# Quad_Board.net
KiCad netlist of a schematic drawn in EAGLE
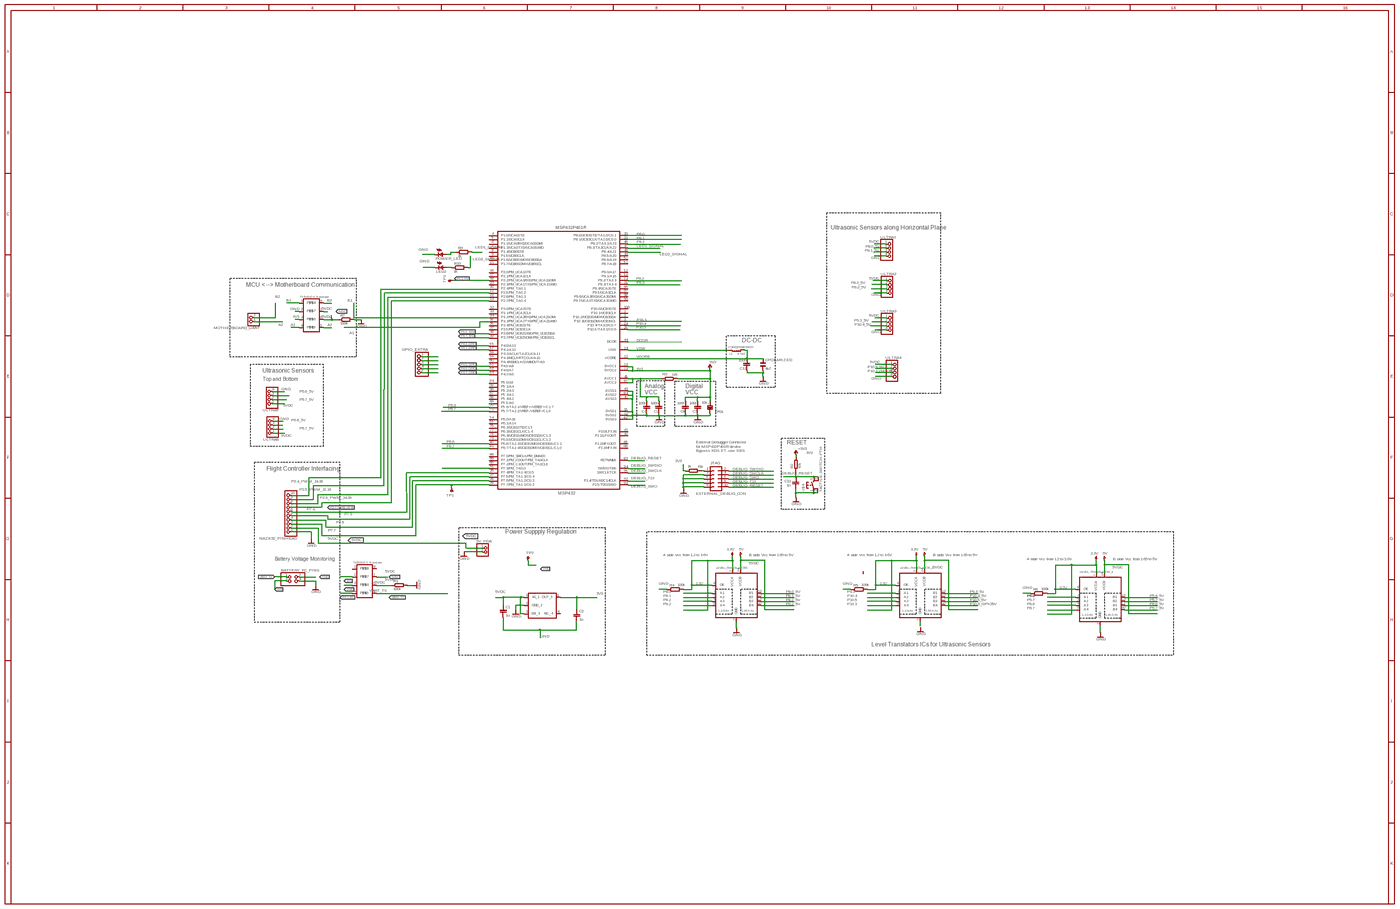
[diagram p0: schematic, sheet 1, overview]
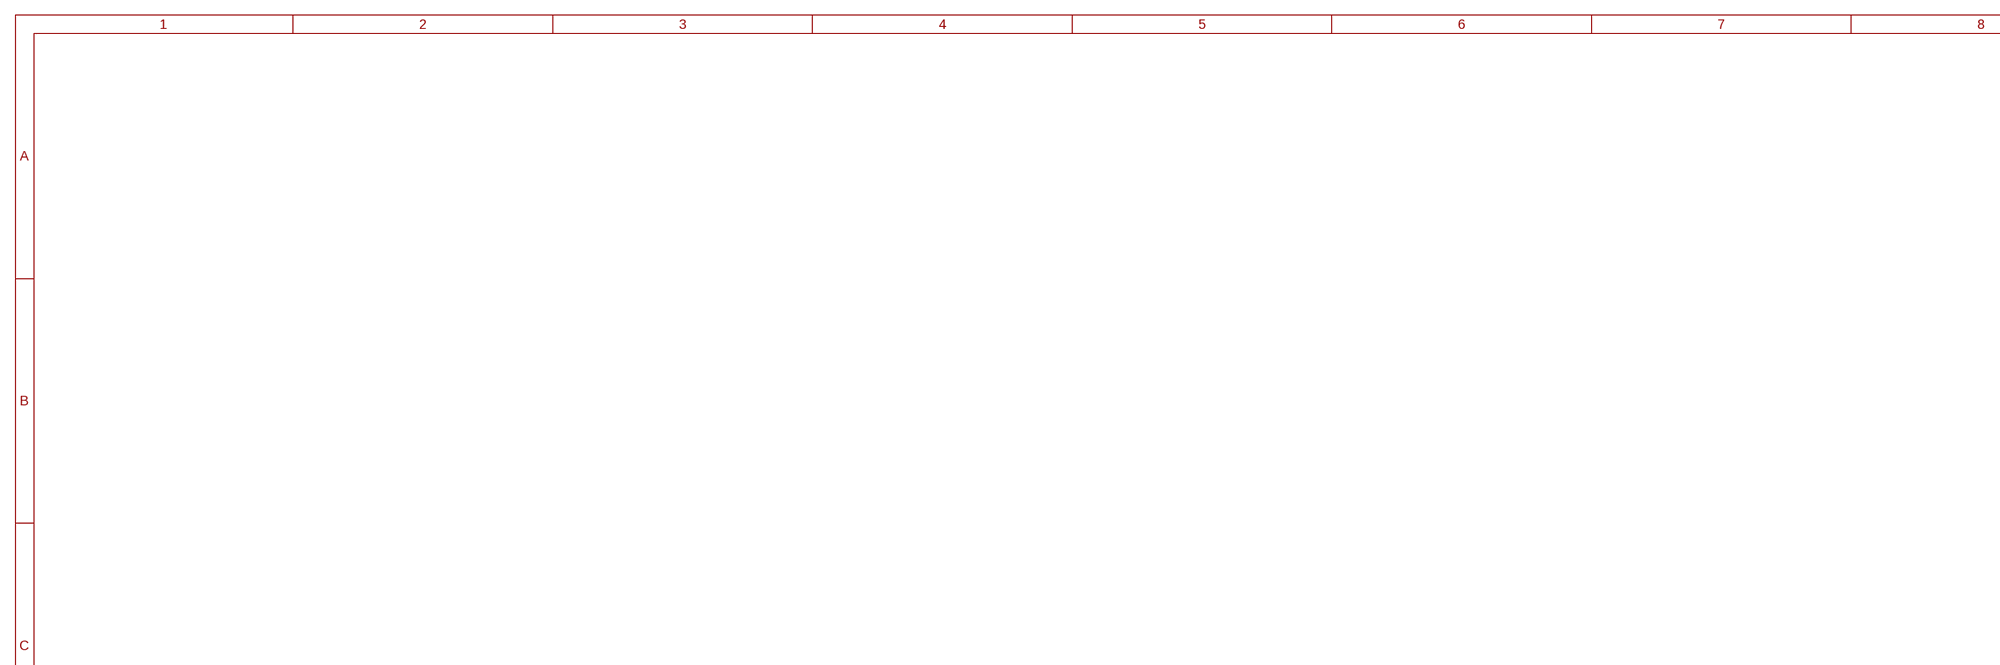
[diagram p1: schematic, sheet 1, part 1 of 4]
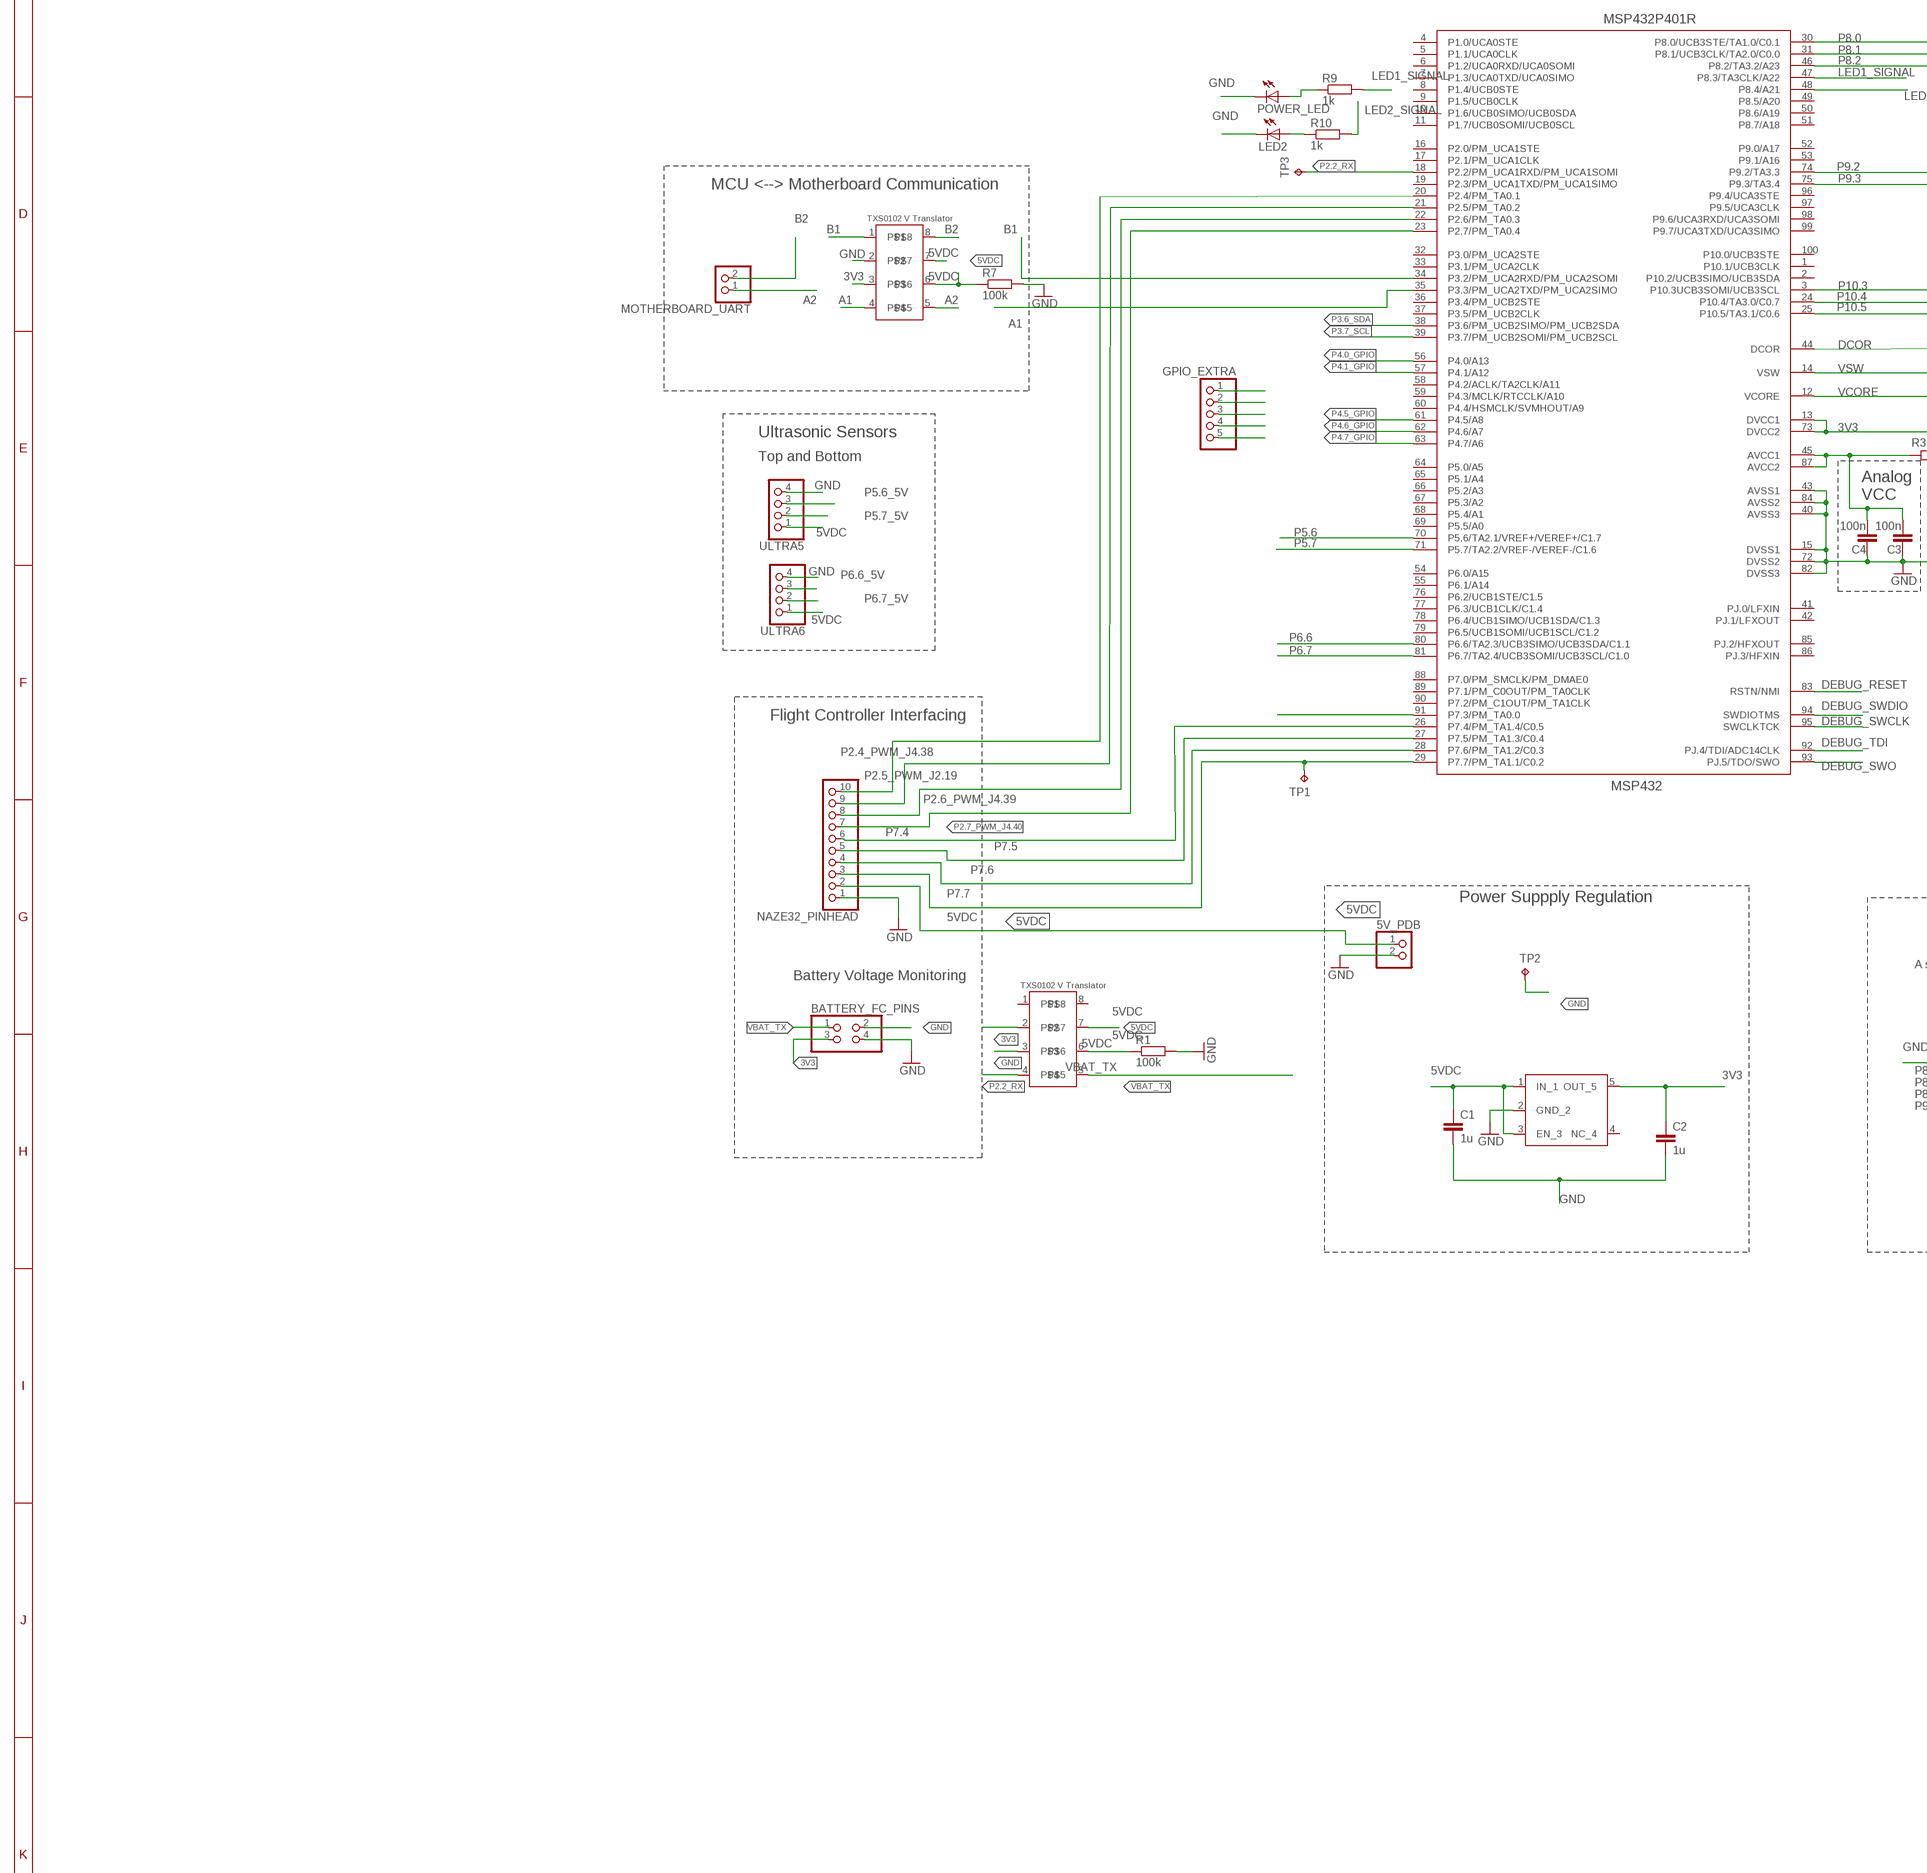
[diagram p2: schematic, sheet 1, part 2 of 4]
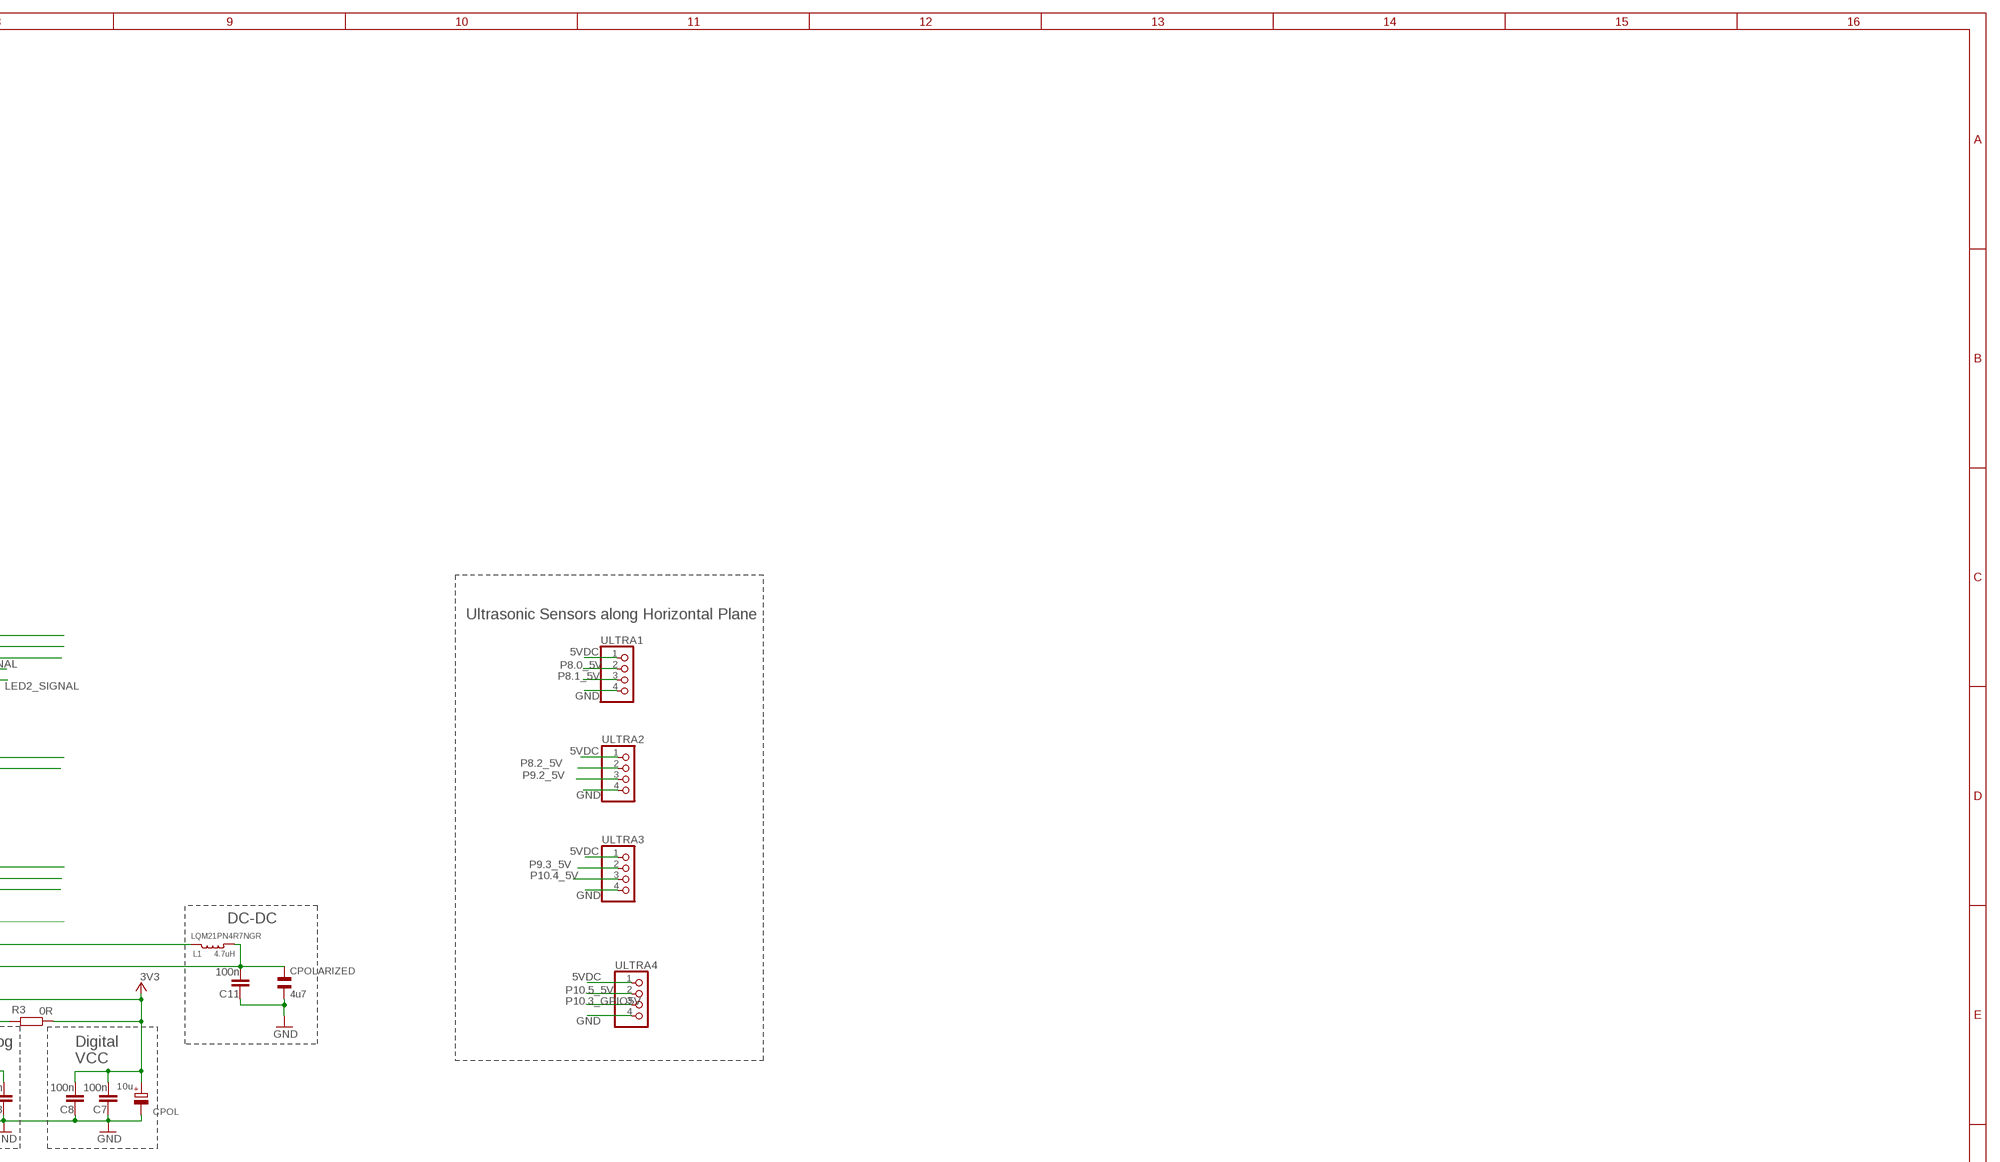
[diagram p3: schematic, sheet 1, part 3 of 4]
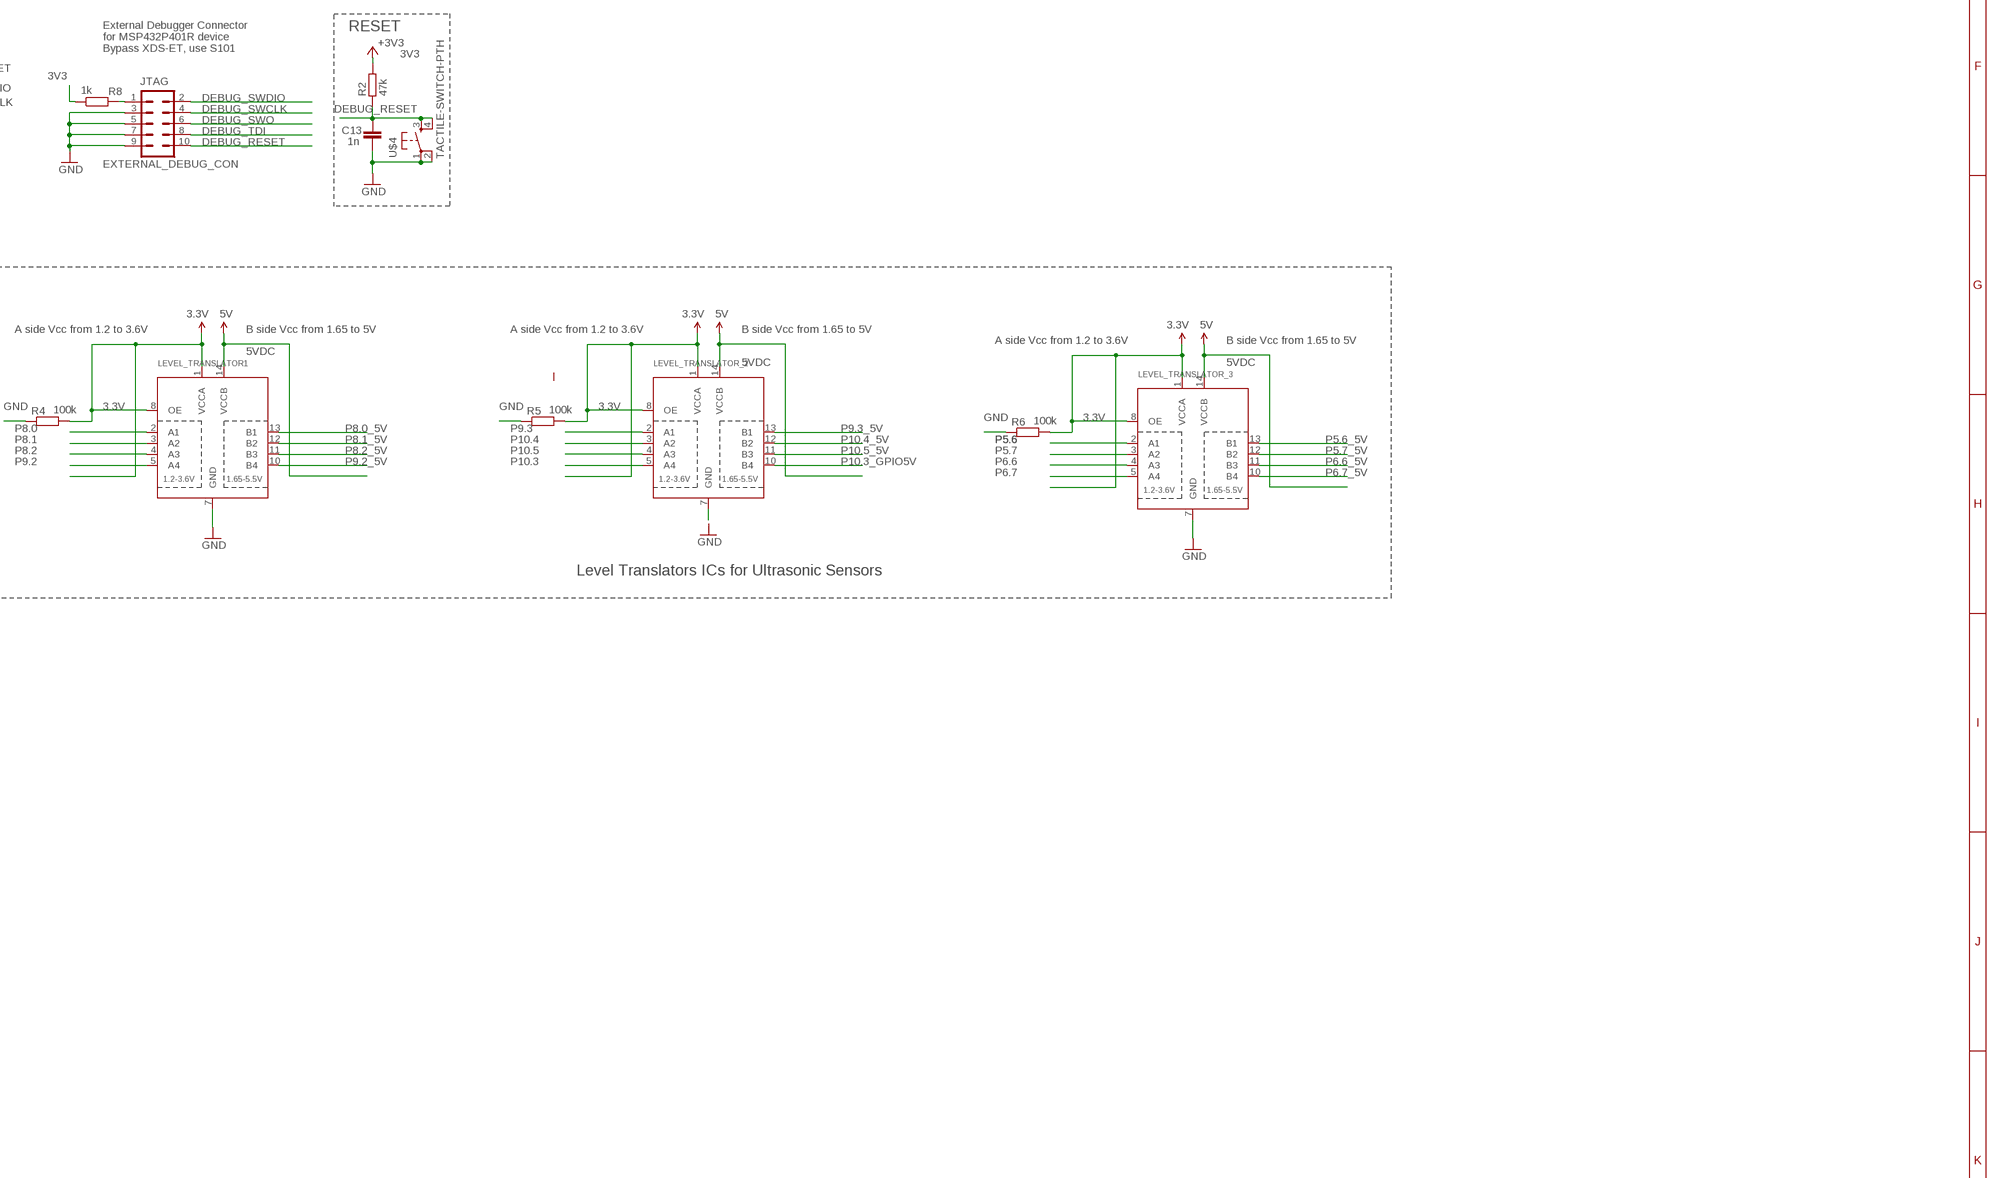
[diagram p4: schematic, sheet 1, part 4 of 4]

(export (version "E")
  (design (tool "Eeschema 10.0.6"))
  (components
    (comp (ref "5V_PDB")
      (value "PINHD-1X2")
      (footprint "eagle-import:1X02")
      (libsource (lib "eagle-import") (part "PINHD-1X2"))
    )
    (comp (ref "BATTERY_FC_PINS")
      (value "PINHD-2X2")
      (footprint "eagle-import:2X02")
      (libsource (lib "eagle-import") (part "PINHD-2X2"))
    )
    (comp (ref "C1")
      (value "1u")
      (footprint "eagle-import:C0805")
      (libsource (lib "eagle-import") (part "C-EUC0805"))
    )
    (comp (ref "C2")
      (value "1u")
      (footprint "eagle-import:C0805")
      (libsource (lib "eagle-import") (part "C-EUC0805"))
    )
    (comp (ref "C3")
      (value "100n")
      (footprint "eagle-import:C0805")
      (libsource (lib "eagle-import") (part "C-EUC0805"))
    )
    (comp (ref "C4")
      (value "100n")
      (footprint "eagle-import:C0805")
      (libsource (lib "eagle-import") (part "C-EUC0805"))
    )
    (comp (ref "C7")
      (value "100n")
      (footprint "eagle-import:C0805")
      (libsource (lib "eagle-import") (part "C-EUC0805"))
    )
    (comp (ref "C8")
      (value "100n")
      (footprint "eagle-import:C0805")
      (libsource (lib "eagle-import") (part "C-EUC0805"))
    )
    (comp (ref "C11")
      (value "100n")
      (footprint "eagle-import:C0805")
      (libsource (lib "eagle-import") (part "C-EUC0805"))
    )
    (comp (ref "C13")
      (value "1n")
      (footprint "eagle-import:C0805")
      (libsource (lib "eagle-import") (part "C-EUC0805"))
    )
    (comp (ref "CPOL")
      (value "10u")
      (footprint "eagle-import:A_3216-18R")
      (libsource (lib "eagle-import") (part "CPOL-EUA/3216-18R"))
    )
    (comp (ref "CPOLARIZED")
      (value "4u7")
      (footprint "eagle-import:CSMD0805")
      (libsource (lib "eagle-import") (part "CSMD0805"))
    )
    (comp (ref "GPIO_EXTRA")
      (value "PINHD-1X5")
      (footprint "eagle-import:1X05")
      (libsource (lib "eagle-import") (part "PINHD-1X5"))
    )
    (comp (ref "JTAG")
      (value "EXTERNAL_DEBUG_CON")
      (footprint "eagle-import:EXTERNAL_DEBUG")
      (libsource (lib "eagle-import") (part "EXTERNAL_DEBUG_CON"))
    )
    (comp (ref "L1")
      (value "4.7uH")
      (footprint "eagle-import:0806")
      (libsource (lib "eagle-import") (part "LQM2MP_G0"))
    )
    (comp (ref "LED2")
      (value "LED_E")
      (footprint "eagle-import:LED_1206")
      (libsource (lib "eagle-import") (part "LED_E"))
    )
    (comp (ref "LEVEL_TRANSLATOR1")
      (value "TXB0104PWRSOIC14")
      (footprint "eagle-import:SO14")
      (libsource (lib "eagle-import") (part "TXB0104PWRSOIC14"))
    )
    (comp (ref "LEVEL_TRANSLATOR_2")
      (value "TXB0104PWRSOIC14")
      (footprint "eagle-import:SO14")
      (libsource (lib "eagle-import") (part "TXB0104PWRSOIC14"))
    )
    (comp (ref "LEVEL_TRANSLATOR_3")
      (value "TXB0104PWRSOIC14")
      (footprint "eagle-import:SO14")
      (libsource (lib "eagle-import") (part "TXB0104PWRSOIC14"))
    )
    (comp (ref "MOTHERBOARD_UART")
      (value "PINHD-1X2")
      (footprint "eagle-import:1X02")
      (libsource (lib "eagle-import") (part "PINHD-1X2"))
    )
    (comp (ref "MSP432P401R")
      (value "MSP432")
      (footprint "eagle-import:PZ100")
      (libsource (lib "eagle-import") (part "MSP432"))
    )
    (comp (ref "NAZE32_PINHEAD")
      (value "PINHD-1X10")
      (footprint "eagle-import:1X10")
      (libsource (lib "eagle-import") (part "PINHD-1X10"))
    )
    (comp (ref "POWER_LED")
      (value "LED_E")
      (footprint "eagle-import:LED_1206")
      (libsource (lib "eagle-import") (part "LED_E"))
    )
    (comp (ref "R1")
      (value "100k")
      (footprint "eagle-import:M1206")
      (libsource (lib "eagle-import") (part "resistor_R-EU_M1206"))
    )
    (comp (ref "R2")
      (value "47k")
      (footprint "eagle-import:R1206")
      (libsource (lib "eagle-import") (part "R-EU_R1206"))
    )
    (comp (ref "R3")
      (value "0R")
      (footprint "eagle-import:0402")
      (libsource (lib "eagle-import") (part "R-EU_RM0402"))
    )
    (comp (ref "R4")
      (value "100k")
      (footprint "eagle-import:M1206")
      (libsource (lib "eagle-import") (part "resistor_R-EU_M1206"))
    )
    (comp (ref "R5")
      (value "100k")
      (footprint "eagle-import:M1206")
      (libsource (lib "eagle-import") (part "resistor_R-EU_M1206"))
    )
    (comp (ref "R6")
      (value "100k")
      (footprint "eagle-import:M1206")
      (libsource (lib "eagle-import") (part "resistor_R-EU_M1206"))
    )
    (comp (ref "R7")
      (value "100k")
      (footprint "eagle-import:M1206")
      (libsource (lib "eagle-import") (part "resistor_R-EU_M1206"))
    )
    (comp (ref "R8")
      (value "1k")
      (footprint "eagle-import:R1206")
      (libsource (lib "eagle-import") (part "R-EU_R1206"))
    )
    (comp (ref "R9")
      (value "1k")
      (footprint "eagle-import:M0805")
      (libsource (lib "eagle-import") (part "resistor_R-EU_M0805"))
    )
    (comp (ref "R10")
      (value "1k")
      (footprint "eagle-import:M0805")
      (libsource (lib "eagle-import") (part "resistor_R-EU_M0805"))
    )
    (comp (ref "TP1")
      (value "TPB1,27")
      (footprint "eagle-import:B1,27")
      (libsource (lib "eagle-import") (part "TPB1,27"))
    )
    (comp (ref "TP2")
      (value "TPB2,54")
      (footprint "eagle-import:B2,54")
      (libsource (lib "eagle-import") (part "TPB2,54"))
    )
    (comp (ref "TP3")
      (value "TPB1,27")
      (footprint "eagle-import:B1,27")
      (libsource (lib "eagle-import") (part "TPB1,27"))
    )
    (comp (ref "U$1")
      (value "TXS0102")
      (footprint "eagle-import:DCT_R-PDSO-G8")
      (libsource (lib "eagle-import") (part "TXS0102"))
    )
    (comp (ref "U$2")
      (value "TLV733P")
      (footprint "eagle-import:SOT23-5")
      (libsource (lib "eagle-import") (part "TLV733P"))
    )
    (comp (ref "U$3")
      (value "TXS0102")
      (footprint "eagle-import:DCT_R-PDSO-G8")
      (libsource (lib "eagle-import") (part "TXS0102"))
    )
    (comp (ref "U$4")
      (value "TACTILE-SWITCH-PTH")
      (footprint "eagle-import:TAC-SWITCH-PTH")
      (libsource (lib "eagle-import") (part "TACTILE-SWITCH-PTH"))
    )
    (comp (ref "ULTRA1")
      (value "PINHD-1X4")
      (footprint "eagle-import:1X04")
      (libsource (lib "eagle-import") (part "PINHD-1X4"))
    )
    (comp (ref "ULTRA2")
      (value "PINHD-1X4")
      (footprint "eagle-import:1X04")
      (libsource (lib "eagle-import") (part "PINHD-1X4"))
    )
    (comp (ref "ULTRA3")
      (value "PINHD-1X4")
      (footprint "eagle-import:1X04")
      (libsource (lib "eagle-import") (part "PINHD-1X4"))
    )
    (comp (ref "ULTRA4")
      (value "PINHD-1X4")
      (footprint "eagle-import:1X04")
      (libsource (lib "eagle-import") (part "PINHD-1X4"))
    )
    (comp (ref "ULTRA5")
      (value "PINHD-1X4")
      (footprint "eagle-import:1X04")
      (libsource (lib "eagle-import") (part "PINHD-1X4"))
    )
    (comp (ref "ULTRA6")
      (value "PINHD-1X4")
      (footprint "eagle-import:1X04")
      (libsource (lib "eagle-import") (part "PINHD-1X4"))
    )
  )
  (nets
    (net (code "1") (name "/A1") (class "Default")
      (node (ref "MSP432P401R") (pin "35") (pinfunction "P3.3/PM_UCA2TXD/PM_UCA2SIMO_35") (pintype "power_in"))
      (node (ref "U$1") (pin "4") (pinfunction "P$4_4") (pintype "bidirectional"))
    )
    (net (code "2") (name "/A2") (class "Default")
      (node (ref "MOTHERBOARD_UART") (pin "1") (pinfunction "1_1") (pintype "passive"))
      (node (ref "U$1") (pin "5") (pinfunction "P$5_5") (pintype "bidirectional"))
    )
    (net (code "3") (name "/B1") (class "Default")
      (node (ref "MSP432P401R") (pin "34") (pinfunction "P3.2/PM_UCA2RXD/PM_UCA2SOMI_34") (pintype "power_in"))
      (node (ref "U$1") (pin "1") (pinfunction "P$1_1") (pintype "bidirectional"))
    )
    (net (code "4") (name "/B2") (class "Default")
      (node (ref "MOTHERBOARD_UART") (pin "2") (pinfunction "2_2") (pintype "passive"))
      (node (ref "U$1") (pin "8") (pinfunction "P$8_8") (pintype "bidirectional"))
    )
    (net (code "5") (name "/DCOR") (class "Default")
      (node (ref "MSP432P401R") (pin "44") (pinfunction "DCOR_44") (pintype "power_in"))
    )
    (net (code "6") (name "/DEBUG_RESET") (class "Default")
      (node (ref "C13") (pin "1") (pinfunction "1_1") (pintype "passive"))
      (node (ref "JTAG") (pin "10") (pinfunction "10_10") (pintype "passive"))
      (node (ref "MSP432P401R") (pin "83") (pinfunction "RSTN/NMI_83") (pintype "power_in"))
      (node (ref "R2") (pin "1") (pinfunction "1_1") (pintype "passive"))
      (node (ref "U$4") (pin "3") (pinfunction "3_3") (pintype "passive"))
      (node (ref "U$4") (pin "4") (pinfunction "4_4") (pintype "passive"))
    )
    (net (code "7") (name "/DEBUG_SWCLK") (class "Default")
      (node (ref "JTAG") (pin "4") (pinfunction "4_4") (pintype "passive"))
      (node (ref "MSP432P401R") (pin "95") (pinfunction "SWCLKTCK_95") (pintype "power_in"))
    )
    (net (code "8") (name "/DEBUG_SWDIO") (class "Default")
      (node (ref "JTAG") (pin "2") (pinfunction "2_2") (pintype "passive"))
      (node (ref "MSP432P401R") (pin "94") (pinfunction "SWDIOTMS_94") (pintype "power_in"))
    )
    (net (code "9") (name "/DEBUG_SWO") (class "Default")
      (node (ref "JTAG") (pin "6") (pinfunction "6_6") (pintype "passive"))
      (node (ref "MSP432P401R") (pin "93") (pinfunction "PJ.5/TDO/SWO_93") (pintype "power_in"))
    )
    (net (code "10") (name "/DEBUG_TDI") (class "Default")
      (node (ref "JTAG") (pin "8") (pinfunction "8_8") (pintype "passive"))
      (node (ref "MSP432P401R") (pin "92") (pinfunction "PJ.4/TDI/ADC14CLK_92") (pintype "power_in"))
    )
    (net (code "11") (name "/LED1_SIGNAL") (class "Default")
      (node (ref "MSP432P401R") (pin "47") (pinfunction "P8.3/TA3CLK/A22_47") (pintype "power_in"))
      (node (ref "R9") (pin "2") (pinfunction "2_2") (pintype "passive"))
    )
    (net (code "12") (name "/LED2_SIGNAL") (class "Default")
      (node (ref "MSP432P401R") (pin "48") (pinfunction "P8.4/A21_48") (pintype "power_in"))
      (node (ref "R10") (pin "2") (pinfunction "2_2") (pintype "passive"))
    )
    (net (code "13") (name "/P1.0{slash}UCA0STE") (class "Default")
      (node (ref "MSP432P401R") (pin "4") (pinfunction "P1.0/UCA0STE_4") (pintype "power_in"))
    )
    (net (code "14") (name "/P1.1{slash}UCA0CLK") (class "Default")
      (node (ref "MSP432P401R") (pin "5") (pinfunction "P1.1/UCA0CLK_5") (pintype "power_in"))
    )
    (net (code "15") (name "/P1.2{slash}UCA0RXD{slash}UCA0SOMI") (class "Default")
      (node (ref "MSP432P401R") (pin "6") (pinfunction "P1.2/UCA0RXD/UCA0SOMI_6") (pintype "power_in"))
    )
    (net (code "16") (name "/P1.3{slash}UCA0TXD{slash}UCA0SIMO") (class "Default")
      (node (ref "MSP432P401R") (pin "7") (pinfunction "P1.3/UCA0TXD/UCA0SIMO_7") (pintype "power_in"))
    )
    (net (code "17") (name "/P1.4{slash}UCB0STE") (class "Default")
      (node (ref "MSP432P401R") (pin "8") (pinfunction "P1.4/UCB0STE_8") (pintype "power_in"))
    )
    (net (code "18") (name "/P1.5{slash}UCB0CLK") (class "Default")
      (node (ref "MSP432P401R") (pin "9") (pinfunction "P1.5/UCB0CLK_9") (pintype "power_in"))
    )
    (net (code "19") (name "/P1.6{slash}UCB0SIMO{slash}UCB0SDA") (class "Default")
      (node (ref "MSP432P401R") (pin "10") (pinfunction "P1.6/UCB0SIMO/UCB0SDA_10") (pintype "power_in"))
    )
    (net (code "20") (name "/P1.7{slash}UCB0SOMI{slash}UCB0SCL") (class "Default")
      (node (ref "MSP432P401R") (pin "11") (pinfunction "P1.7/UCB0SOMI/UCB0SCL_11") (pintype "power_in"))
    )
    (net (code "21") (name "/P2.0{slash}PM_UCA1STE") (class "Default")
      (node (ref "MSP432P401R") (pin "16") (pinfunction "P2.0/PM_UCA1STE_16") (pintype "power_in"))
    )
    (net (code "22") (name "/P2.1{slash}PM_UCA1CLK") (class "Default")
      (node (ref "MSP432P401R") (pin "17") (pinfunction "P2.1/PM_UCA1CLK_17") (pintype "power_in"))
    )
    (net (code "23") (name "/P2.3{slash}PM_UCA1TXD{slash}PM_UCA1SIMO") (class "Default")
      (node (ref "MSP432P401R") (pin "19") (pinfunction "P2.3/PM_UCA1TXD/PM_UCA1SIMO_19") (pintype "power_in"))
    )
    (net (code "24") (name "/P2.4_PWM_J4.38") (class "Default")
      (node (ref "MSP432P401R") (pin "20") (pinfunction "P2.4/PM_TA0.1_20") (pintype "power_in"))
      (node (ref "NAZE32_PINHEAD") (pin "10") (pinfunction "10_10") (pintype "passive"))
    )
    (net (code "25") (name "/P2.5_PWM_J2.19") (class "Default")
      (node (ref "MSP432P401R") (pin "21") (pinfunction "P2.5/PM_TA0.2_21") (pintype "power_in"))
      (node (ref "NAZE32_PINHEAD") (pin "9") (pinfunction "9_9") (pintype "passive"))
    )
    (net (code "26") (name "/P2.6_PWM_J4.39") (class "Default")
      (node (ref "MSP432P401R") (pin "22") (pinfunction "P2.6/PM_TA0.3_22") (pintype "power_in"))
      (node (ref "NAZE32_PINHEAD") (pin "8") (pinfunction "8_8") (pintype "passive"))
    )
    (net (code "27") (name "/P3.0{slash}PM_UCA2STE") (class "Default")
      (node (ref "MSP432P401R") (pin "32") (pinfunction "P3.0/PM_UCA2STE_32") (pintype "power_in"))
    )
    (net (code "28") (name "/P3.1{slash}PM_UCA2CLK") (class "Default")
      (node (ref "MSP432P401R") (pin "33") (pinfunction "P3.1/PM_UCA2CLK_33") (pintype "power_in"))
    )
    (net (code "29") (name "/P3.4{slash}PM_UCB2STE") (class "Default")
      (node (ref "MSP432P401R") (pin "36") (pinfunction "P3.4/PM_UCB2STE_36") (pintype "power_in"))
    )
    (net (code "30") (name "/P3.5{slash}PM_UCB2CLK") (class "Default")
      (node (ref "MSP432P401R") (pin "37") (pinfunction "P3.5/PM_UCB2CLK_37") (pintype "power_in"))
    )
    (net (code "31") (name "/P4.2{slash}ACLK{slash}TA2CLK{slash}A11") (class "Default")
      (node (ref "MSP432P401R") (pin "58") (pinfunction "P4.2/ACLK/TA2CLK/A11_58") (pintype "power_in"))
    )
    (net (code "32") (name "/P4.3{slash}MCLK{slash}RTCCLK{slash}A10") (class "Default")
      (node (ref "MSP432P401R") (pin "59") (pinfunction "P4.3/MCLK/RTCCLK/A10_59") (pintype "power_in"))
    )
    (net (code "33") (name "/P4.4{slash}HSMCLK{slash}SVMHOUT{slash}A9") (class "Default")
      (node (ref "MSP432P401R") (pin "60") (pinfunction "P4.4/HSMCLK/SVMHOUT/A9_60") (pintype "power_in"))
    )
    (net (code "34") (name "/P5.0{slash}A5") (class "Default")
      (node (ref "MSP432P401R") (pin "64") (pinfunction "P5.0/A5_64") (pintype "power_in"))
    )
    (net (code "35") (name "/P5.1{slash}A4") (class "Default")
      (node (ref "MSP432P401R") (pin "65") (pinfunction "P5.1/A4_65") (pintype "power_in"))
    )
    (net (code "36") (name "/P5.2{slash}A3") (class "Default")
      (node (ref "MSP432P401R") (pin "66") (pinfunction "P5.2/A3_66") (pintype "power_in"))
    )
    (net (code "37") (name "/P5.3{slash}A2") (class "Default")
      (node (ref "MSP432P401R") (pin "67") (pinfunction "P5.3/A2_67") (pintype "power_in"))
    )
    (net (code "38") (name "/P5.4{slash}A1") (class "Default")
      (node (ref "MSP432P401R") (pin "68") (pinfunction "P5.4/A1_68") (pintype "power_in"))
    )
    (net (code "39") (name "/P5.5{slash}A0") (class "Default")
      (node (ref "MSP432P401R") (pin "69") (pinfunction "P5.5/A0_69") (pintype "power_in"))
    )
    (net (code "40") (name "/P5.6") (class "Default")
      (node (ref "LEVEL_TRANSLATOR_3") (pin "2") (pinfunction "A1_2") (pintype "bidirectional"))
      (node (ref "MSP432P401R") (pin "70") (pinfunction "P5.6/TA2.1/VREF+/VEREF+/C1.7_70") (pintype "power_in"))
    )
    (net (code "41") (name "/P5.6_5V") (class "Default")
      (node (ref "LEVEL_TRANSLATOR_3") (pin "13") (pinfunction "B1_13") (pintype "bidirectional"))
      (node (ref "ULTRA5") (pin "3") (pinfunction "3_3") (pintype "passive"))
    )
    (net (code "42") (name "/P5.7") (class "Default")
      (node (ref "LEVEL_TRANSLATOR_3") (pin "3") (pinfunction "A2_3") (pintype "bidirectional"))
      (node (ref "MSP432P401R") (pin "71") (pinfunction "P5.7/TA2.2/VREF-/VEREF-/C1.6_71") (pintype "power_in"))
    )
    (net (code "43") (name "/P5.7_5V") (class "Default")
      (node (ref "LEVEL_TRANSLATOR_3") (pin "12") (pinfunction "B2_12") (pintype "bidirectional"))
      (node (ref "ULTRA5") (pin "2") (pinfunction "2_2") (pintype "passive"))
    )
    (net (code "44") (name "/P6.0{slash}A15") (class "Default")
      (node (ref "MSP432P401R") (pin "54") (pinfunction "P6.0/A15_54") (pintype "power_in"))
    )
    (net (code "45") (name "/P6.1{slash}A14") (class "Default")
      (node (ref "MSP432P401R") (pin "55") (pinfunction "P6.1/A14_55") (pintype "power_in"))
    )
    (net (code "46") (name "/P6.2{slash}UCB1STE{slash}C1.5") (class "Default")
      (node (ref "MSP432P401R") (pin "76") (pinfunction "P6.2/UCB1STE/C1.5_76") (pintype "power_in"))
    )
    (net (code "47") (name "/P6.3{slash}UCB1CLK{slash}C1.4") (class "Default")
      (node (ref "MSP432P401R") (pin "77") (pinfunction "P6.3/UCB1CLK/C1.4_77") (pintype "power_in"))
    )
    (net (code "48") (name "/P6.4{slash}UCB1SIMO{slash}UCB1SDA{slash}C1.3") (class "Default")
      (node (ref "MSP432P401R") (pin "78") (pinfunction "P6.4/UCB1SIMO/UCB1SDA/C1.3_78") (pintype "power_in"))
    )
    (net (code "49") (name "/P6.5{slash}UCB1SOMI{slash}UCB1SCL{slash}C1.2") (class "Default")
      (node (ref "MSP432P401R") (pin "79") (pinfunction "P6.5/UCB1SOMI/UCB1SCL/C1.2_79") (pintype "power_in"))
    )
    (net (code "50") (name "/P6.6") (class "Default")
      (node (ref "LEVEL_TRANSLATOR_3") (pin "4") (pinfunction "A3_4") (pintype "bidirectional"))
      (node (ref "MSP432P401R") (pin "80") (pinfunction "P6.6/TA2.3/UCB3SIMO/UCB3SDA/C1.1_80") (pintype "power_in"))
    )
    (net (code "51") (name "/P6.6_5V") (class "Default")
      (node (ref "LEVEL_TRANSLATOR_3") (pin "11") (pinfunction "B3_11") (pintype "bidirectional"))
      (node (ref "ULTRA6") (pin "3") (pinfunction "3_3") (pintype "passive"))
    )
    (net (code "52") (name "/P6.7") (class "Default")
      (node (ref "LEVEL_TRANSLATOR_3") (pin "5") (pinfunction "A4_5") (pintype "bidirectional"))
      (node (ref "MSP432P401R") (pin "81") (pinfunction "P6.7/TA2.4/UCB3SOMI/UCB3SCL/C1.0_81") (pintype "power_in"))
    )
    (net (code "53") (name "/P6.7_5V") (class "Default")
      (node (ref "LEVEL_TRANSLATOR_3") (pin "10") (pinfunction "B4_10") (pintype "bidirectional"))
      (node (ref "ULTRA6") (pin "2") (pinfunction "2_2") (pintype "passive"))
    )
    (net (code "54") (name "/P7.0{slash}PM_SMCLK{slash}PM_DMAE0") (class "Default")
      (node (ref "MSP432P401R") (pin "88") (pinfunction "P7.0/PM_SMCLK/PM_DMAE0_88") (pintype "power_in"))
    )
    (net (code "55") (name "/P7.1{slash}PM_C0OUT{slash}PM_TA0CLK") (class "Default")
      (node (ref "MSP432P401R") (pin "89") (pinfunction "P7.1/PM_C0OUT/PM_TA0CLK_89") (pintype "power_in"))
    )
    (net (code "56") (name "/P7.2{slash}PM_C1OUT{slash}PM_TA1CLK") (class "Default")
      (node (ref "MSP432P401R") (pin "90") (pinfunction "P7.2/PM_C1OUT/PM_TA1CLK_90") (pintype "power_in"))
    )
    (net (code "57") (name "/P7.4") (class "Default")
      (node (ref "MSP432P401R") (pin "26") (pinfunction "P7.4/PM_TA1.4/C0.5_26") (pintype "power_in"))
      (node (ref "NAZE32_PINHEAD") (pin "6") (pinfunction "6_6") (pintype "passive"))
    )
    (net (code "58") (name "/P7.5") (class "Default")
      (node (ref "MSP432P401R") (pin "27") (pinfunction "P7.5/PM_TA1.3/C0.4_27") (pintype "power_in"))
      (node (ref "NAZE32_PINHEAD") (pin "5") (pinfunction "5_5") (pintype "passive"))
    )
    (net (code "59") (name "/P7.6") (class "Default")
      (node (ref "MSP432P401R") (pin "28") (pinfunction "P7.6/PM_TA1.2/C0.3_28") (pintype "power_in"))
      (node (ref "NAZE32_PINHEAD") (pin "4") (pinfunction "4_4") (pintype "passive"))
    )
    (net (code "60") (name "/P7.7") (class "Default")
      (node (ref "MSP432P401R") (pin "29") (pinfunction "P7.7/PM_TA1.1/C0.2_29") (pintype "power_in"))
      (node (ref "NAZE32_PINHEAD") (pin "3") (pinfunction "3_3") (pintype "passive"))
      (node (ref "TP1") (pin "TP") (pinfunction "TP_TP") (pintype "input"))
    )
    (net (code "61") (name "/P8.0") (class "Default")
      (node (ref "LEVEL_TRANSLATOR1") (pin "2") (pinfunction "A1_2") (pintype "bidirectional"))
      (node (ref "MSP432P401R") (pin "30") (pinfunction "P8.0/UCB3STE/TA1.0/C0.1_30") (pintype "power_in"))
    )
    (net (code "62") (name "/P8.0_5V") (class "Default")
      (node (ref "LEVEL_TRANSLATOR1") (pin "13") (pinfunction "B1_13") (pintype "bidirectional"))
      (node (ref "ULTRA1") (pin "2") (pinfunction "2_2") (pintype "passive"))
    )
    (net (code "63") (name "/P8.1") (class "Default")
      (node (ref "LEVEL_TRANSLATOR1") (pin "3") (pinfunction "A2_3") (pintype "bidirectional"))
      (node (ref "MSP432P401R") (pin "31") (pinfunction "P8.1/UCB3CLK/TA2.0/C0.0_31") (pintype "power_in"))
    )
    (net (code "64") (name "/P8.1_5V") (class "Default")
      (node (ref "LEVEL_TRANSLATOR1") (pin "12") (pinfunction "B2_12") (pintype "bidirectional"))
      (node (ref "ULTRA1") (pin "3") (pinfunction "3_3") (pintype "passive"))
    )
    (net (code "65") (name "/P8.2") (class "Default")
      (node (ref "LEVEL_TRANSLATOR1") (pin "4") (pinfunction "A3_4") (pintype "bidirectional"))
      (node (ref "MSP432P401R") (pin "46") (pinfunction "P8.2/TA3.2/A23_46") (pintype "power_in"))
    )
    (net (code "66") (name "/P8.2_5V") (class "Default")
      (node (ref "LEVEL_TRANSLATOR1") (pin "11") (pinfunction "B3_11") (pintype "bidirectional"))
      (node (ref "ULTRA2") (pin "2") (pinfunction "2_2") (pintype "passive"))
    )
    (net (code "67") (name "/P8.5{slash}A20") (class "Default")
      (node (ref "MSP432P401R") (pin "49") (pinfunction "P8.5/A20_49") (pintype "power_in"))
    )
    (net (code "68") (name "/P8.6{slash}A19") (class "Default")
      (node (ref "MSP432P401R") (pin "50") (pinfunction "P8.6/A19_50") (pintype "power_in"))
    )
    (net (code "69") (name "/P8.7{slash}A18") (class "Default")
      (node (ref "MSP432P401R") (pin "51") (pinfunction "P8.7/A18_51") (pintype "power_in"))
    )
    (net (code "70") (name "/P9.0{slash}A17") (class "Default")
      (node (ref "MSP432P401R") (pin "52") (pinfunction "P9.0/A17_52") (pintype "power_in"))
    )
    (net (code "71") (name "/P9.1{slash}A16") (class "Default")
      (node (ref "MSP432P401R") (pin "53") (pinfunction "P9.1/A16_53") (pintype "power_in"))
    )
    (net (code "72") (name "/P9.2") (class "Default")
      (node (ref "LEVEL_TRANSLATOR1") (pin "5") (pinfunction "A4_5") (pintype "bidirectional"))
      (node (ref "MSP432P401R") (pin "74") (pinfunction "P9.2/TA3.3_74") (pintype "power_in"))
    )
    (net (code "73") (name "/P9.2_5V") (class "Default")
      (node (ref "LEVEL_TRANSLATOR1") (pin "10") (pinfunction "B4_10") (pintype "bidirectional"))
      (node (ref "ULTRA2") (pin "3") (pinfunction "3_3") (pintype "passive"))
    )
    (net (code "74") (name "/P9.3") (class "Default")
      (node (ref "LEVEL_TRANSLATOR_2") (pin "2") (pinfunction "A1_2") (pintype "bidirectional"))
      (node (ref "MSP432P401R") (pin "75") (pinfunction "P9.3/TA3.4_75") (pintype "power_in"))
    )
    (net (code "75") (name "/P9.3_5V") (class "Default")
      (node (ref "LEVEL_TRANSLATOR_2") (pin "13") (pinfunction "B1_13") (pintype "bidirectional"))
      (node (ref "ULTRA3") (pin "2") (pinfunction "2_2") (pintype "passive"))
    )
    (net (code "76") (name "/P9.4{slash}UCA3STE") (class "Default")
      (node (ref "MSP432P401R") (pin "96") (pinfunction "P9.4/UCA3STE_96") (pintype "power_in"))
    )
    (net (code "77") (name "/P9.5{slash}UCA3CLK") (class "Default")
      (node (ref "MSP432P401R") (pin "97") (pinfunction "P9.5/UCA3CLK_97") (pintype "power_in"))
    )
    (net (code "78") (name "/P9.6{slash}UCA3RXD{slash}UCA3SOMI") (class "Default")
      (node (ref "MSP432P401R") (pin "98") (pinfunction "P9.6/UCA3RXD/UCA3SOMI_98") (pintype "power_in"))
    )
    (net (code "79") (name "/P9.7{slash}UCA3TXD{slash}UCA3SIMO") (class "Default")
      (node (ref "MSP432P401R") (pin "99") (pinfunction "P9.7/UCA3TXD/UCA3SIMO_99") (pintype "power_in"))
    )
    (net (code "80") (name "/P10.0{slash}UCB3STE") (class "Default")
      (node (ref "MSP432P401R") (pin "100") (pinfunction "P10.0/UCB3STE_100") (pintype "power_in"))
    )
    (net (code "81") (name "/P10.1{slash}UCB3CLK") (class "Default")
      (node (ref "MSP432P401R") (pin "1") (pinfunction "P10.1/UCB3CLK_1") (pintype "power_in"))
    )
    (net (code "82") (name "/P10.2{slash}UCB3SIMO{slash}UCB3SDA") (class "Default")
      (node (ref "MSP432P401R") (pin "2") (pinfunction "P10.2/UCB3SIMO/UCB3SDA_2") (pintype "power_in"))
    )
    (net (code "83") (name "/P10.3") (class "Default")
      (node (ref "LEVEL_TRANSLATOR_2") (pin "5") (pinfunction "A4_5") (pintype "bidirectional"))
      (node (ref "MSP432P401R") (pin "3") (pinfunction "P10.3UCB3SOMI/UCB3SCL_3") (pintype "power_in"))
    )
    (net (code "84") (name "/P10.3_GPIO5V") (class "Default")
      (node (ref "LEVEL_TRANSLATOR_2") (pin "10") (pinfunction "B4_10") (pintype "bidirectional"))
      (node (ref "ULTRA4") (pin "3") (pinfunction "3_3") (pintype "passive"))
    )
    (net (code "85") (name "/P10.4") (class "Default")
      (node (ref "LEVEL_TRANSLATOR_2") (pin "3") (pinfunction "A2_3") (pintype "bidirectional"))
      (node (ref "MSP432P401R") (pin "24") (pinfunction "P10.4/TA3.0/C0.7_24") (pintype "power_in"))
    )
    (net (code "86") (name "/P10.4_5V") (class "Default")
      (node (ref "LEVEL_TRANSLATOR_2") (pin "12") (pinfunction "B2_12") (pintype "bidirectional"))
      (node (ref "ULTRA3") (pin "3") (pinfunction "3_3") (pintype "passive"))
    )
    (net (code "87") (name "/P10.5") (class "Default")
      (node (ref "LEVEL_TRANSLATOR_2") (pin "4") (pinfunction "A3_4") (pintype "bidirectional"))
      (node (ref "MSP432P401R") (pin "25") (pinfunction "P10.5/TA3.1/C0.6_25") (pintype "power_in"))
    )
    (net (code "88") (name "/P10.5_5V") (class "Default")
      (node (ref "LEVEL_TRANSLATOR_2") (pin "11") (pinfunction "B3_11") (pintype "bidirectional"))
      (node (ref "ULTRA4") (pin "2") (pinfunction "2_2") (pintype "passive"))
    )
    (net (code "89") (name "/PJ.0{slash}LFXIN") (class "Default")
      (node (ref "MSP432P401R") (pin "41") (pinfunction "PJ.0/LFXIN_41") (pintype "power_in"))
    )
    (net (code "90") (name "/PJ.1{slash}LFXOUT") (class "Default")
      (node (ref "MSP432P401R") (pin "42") (pinfunction "PJ.1/LFXOUT_42") (pintype "power_in"))
    )
    (net (code "91") (name "/PJ.2{slash}HFXOUT") (class "Default")
      (node (ref "MSP432P401R") (pin "85") (pinfunction "PJ.2/HFXOUT_85") (pintype "power_in"))
    )
    (net (code "92") (name "/PJ.3{slash}HFXIN") (class "Default")
      (node (ref "MSP432P401R") (pin "86") (pinfunction "PJ.3/HFXIN_86") (pintype "power_in"))
    )
    (net (code "93") (name "/VCORE") (class "Default")
      (node (ref "C11") (pin "1") (pinfunction "1_1") (pintype "passive"))
      (node (ref "CPOLARIZED") (pin "1") (pinfunction "1_1") (pintype "passive"))
      (node (ref "L1") (pin "1") (pinfunction "1_1") (pintype "passive"))
      (node (ref "MSP432P401R") (pin "12") (pinfunction "VCORE_12") (pintype "power_in"))
    )
    (net (code "94") (name "/VSW") (class "Default")
      (node (ref "L1") (pin "2") (pinfunction "2_2") (pintype "passive"))
      (node (ref "MSP432P401R") (pin "14") (pinfunction "VSW_14") (pintype "power_in"))
    )
    (net (code "95") (name "3.3V") (class "Default")
      (node (ref "LEVEL_TRANSLATOR1") (pin "1") (pinfunction "VCCA_1") (pintype "bidirectional"))
      (node (ref "LEVEL_TRANSLATOR1") (pin "8") (pinfunction "OE_8") (pintype "bidirectional"))
      (node (ref "LEVEL_TRANSLATOR_2") (pin "1") (pinfunction "VCCA_1") (pintype "bidirectional"))
      (node (ref "LEVEL_TRANSLATOR_2") (pin "8") (pinfunction "OE_8") (pintype "bidirectional"))
      (node (ref "LEVEL_TRANSLATOR_3") (pin "1") (pinfunction "VCCA_1") (pintype "bidirectional"))
      (node (ref "LEVEL_TRANSLATOR_3") (pin "8") (pinfunction "OE_8") (pintype "bidirectional"))
      (node (ref "R4") (pin "2") (pinfunction "2_2") (pintype "passive"))
      (node (ref "R5") (pin "2") (pinfunction "2_2") (pintype "passive"))
      (node (ref "R6") (pin "2") (pinfunction "2_2") (pintype "passive"))
    )
    (net (code "96") (name "3V3") (class "Default")
      (node (ref "BATTERY_FC_PINS") (pin "3") (pinfunction "3_3") (pintype "passive"))
      (node (ref "C2") (pin "1") (pinfunction "1_1") (pintype "passive"))
      (node (ref "C7") (pin "1") (pinfunction "1_1") (pintype "passive"))
      (node (ref "C8") (pin "1") (pinfunction "1_1") (pintype "passive"))
      (node (ref "CPOL") (pin "+") (pinfunction "+_+") (pintype "passive"))
      (node (ref "MSP432P401R") (pin "13") (pinfunction "DVCC1_13") (pintype "power_in"))
      (node (ref "MSP432P401R") (pin "73") (pinfunction "DVCC2_73") (pintype "power_in"))
      (node (ref "R2") (pin "2") (pinfunction "2_2") (pintype "passive"))
      (node (ref "R3") (pin "1") (pinfunction "1_1") (pintype "passive"))
      (node (ref "R8") (pin "1") (pinfunction "1_1") (pintype "passive"))
      (node (ref "U$1") (pin "3") (pinfunction "P$3_3") (pintype "bidirectional"))
      (node (ref "U$2") (pin "5") (pinfunction "OUT_5_5") (pintype "bidirectional"))
      (node (ref "U$3") (pin "2") (pinfunction "P$2_2") (pintype "bidirectional"))
    )
    (net (code "97") (name "5VDC") (class "Default")
      (node (ref "5V_PDB") (pin "1") (pinfunction "1_1") (pintype "passive"))
      (node (ref "C1") (pin "1") (pinfunction "1_1") (pintype "passive"))
      (node (ref "LEVEL_TRANSLATOR1") (pin "14") (pinfunction "VCCB_14") (pintype "bidirectional"))
      (node (ref "LEVEL_TRANSLATOR_2") (pin "14") (pinfunction "VCCB_14") (pintype "bidirectional"))
      (node (ref "LEVEL_TRANSLATOR_3") (pin "14") (pinfunction "VCCB_14") (pintype "bidirectional"))
      (node (ref "NAZE32_PINHEAD") (pin "2") (pinfunction "2_2") (pintype "passive"))
      (node (ref "R1") (pin "1") (pinfunction "1_1") (pintype "passive"))
      (node (ref "R7") (pin "1") (pinfunction "1_1") (pintype "passive"))
      (node (ref "U$1") (pin "6") (pinfunction "P$6_6") (pintype "bidirectional"))
      (node (ref "U$1") (pin "7") (pinfunction "P$7_7") (pintype "bidirectional"))
      (node (ref "U$2") (pin "1") (pinfunction "IN_1_1") (pintype "bidirectional"))
      (node (ref "U$2") (pin "3") (pinfunction "EN_3_3") (pintype "bidirectional"))
      (node (ref "U$3") (pin "6") (pinfunction "P$6_6") (pintype "bidirectional"))
      (node (ref "U$3") (pin "7") (pinfunction "P$7_7") (pintype "bidirectional"))
      (node (ref "ULTRA1") (pin "1") (pinfunction "1_1") (pintype "passive"))
      (node (ref "ULTRA2") (pin "1") (pinfunction "1_1") (pintype "passive"))
      (node (ref "ULTRA3") (pin "1") (pinfunction "1_1") (pintype "passive"))
      (node (ref "ULTRA4") (pin "1") (pinfunction "1_1") (pintype "passive"))
      (node (ref "ULTRA5") (pin "1") (pinfunction "1_1") (pintype "passive"))
      (node (ref "ULTRA6") (pin "1") (pinfunction "1_1") (pintype "passive"))
    )
    (net (code "98") (name "GND") (class "Default")
      (node (ref "5V_PDB") (pin "2") (pinfunction "2_2") (pintype "passive"))
      (node (ref "BATTERY_FC_PINS") (pin "2") (pinfunction "2_2") (pintype "passive"))
      (node (ref "BATTERY_FC_PINS") (pin "4") (pinfunction "4_4") (pintype "passive"))
      (node (ref "C1") (pin "2") (pinfunction "2_2") (pintype "passive"))
      (node (ref "C11") (pin "2") (pinfunction "2_2") (pintype "passive"))
      (node (ref "C13") (pin "2") (pinfunction "2_2") (pintype "passive"))
      (node (ref "C2") (pin "2") (pinfunction "2_2") (pintype "passive"))
      (node (ref "C3") (pin "2") (pinfunction "2_2") (pintype "passive"))
      (node (ref "C4") (pin "2") (pinfunction "2_2") (pintype "passive"))
      (node (ref "C7") (pin "2") (pinfunction "2_2") (pintype "passive"))
      (node (ref "C8") (pin "2") (pinfunction "2_2") (pintype "passive"))
      (node (ref "CPOL") (pin "-") (pinfunction "-_-") (pintype "passive"))
      (node (ref "CPOLARIZED") (pin "2") (pinfunction "2_2") (pintype "passive"))
      (node (ref "JTAG") (pin "3") (pinfunction "3_3") (pintype "passive"))
      (node (ref "JTAG") (pin "5") (pinfunction "5_5") (pintype "passive"))
      (node (ref "JTAG") (pin "7") (pinfunction "7_7") (pintype "passive"))
      (node (ref "JTAG") (pin "9") (pinfunction "9_9") (pintype "passive"))
      (node (ref "LED2") (pin "C") (pinfunction "C_C") (pintype "passive"))
      (node (ref "LEVEL_TRANSLATOR1") (pin "7") (pinfunction "GND_7") (pintype "bidirectional"))
      (node (ref "LEVEL_TRANSLATOR_2") (pin "7") (pinfunction "GND_7") (pintype "bidirectional"))
      (node (ref "LEVEL_TRANSLATOR_3") (pin "7") (pinfunction "GND_7") (pintype "bidirectional"))
      (node (ref "MSP432P401R") (pin "15") (pinfunction "DVSS1_15") (pintype "power_in"))
      (node (ref "MSP432P401R") (pin "40") (pinfunction "AVSS3_40") (pintype "power_in"))
      (node (ref "MSP432P401R") (pin "43") (pinfunction "AVSS1_43") (pintype "power_in"))
      (node (ref "MSP432P401R") (pin "72") (pinfunction "DVSS2_72") (pintype "power_in"))
      (node (ref "MSP432P401R") (pin "82") (pinfunction "DVSS3_82") (pintype "power_in"))
      (node (ref "MSP432P401R") (pin "84") (pinfunction "AVSS2_84") (pintype "power_in"))
      (node (ref "NAZE32_PINHEAD") (pin "1") (pinfunction "1_1") (pintype "passive"))
      (node (ref "POWER_LED") (pin "C") (pinfunction "C_C") (pintype "passive"))
      (node (ref "R1") (pin "2") (pinfunction "2_2") (pintype "passive"))
      (node (ref "R4") (pin "1") (pinfunction "1_1") (pintype "passive"))
      (node (ref "R5") (pin "1") (pinfunction "1_1") (pintype "passive"))
      (node (ref "R6") (pin "1") (pinfunction "1_1") (pintype "passive"))
      (node (ref "R7") (pin "2") (pinfunction "2_2") (pintype "passive"))
      (node (ref "TP2") (pin "TP") (pinfunction "TP_TP") (pintype "input"))
      (node (ref "U$1") (pin "2") (pinfunction "P$2_2") (pintype "bidirectional"))
      (node (ref "U$2") (pin "2") (pinfunction "GND_2_2") (pintype "bidirectional"))
      (node (ref "U$3") (pin "3") (pinfunction "P$3_3") (pintype "bidirectional"))
      (node (ref "U$4") (pin "1") (pinfunction "1_1") (pintype "passive"))
      (node (ref "U$4") (pin "2") (pinfunction "2_2") (pintype "passive"))
      (node (ref "ULTRA1") (pin "4") (pinfunction "4_4") (pintype "passive"))
      (node (ref "ULTRA2") (pin "4") (pinfunction "4_4") (pintype "passive"))
      (node (ref "ULTRA3") (pin "4") (pinfunction "4_4") (pintype "passive"))
      (node (ref "ULTRA4") (pin "4") (pinfunction "4_4") (pintype "passive"))
      (node (ref "ULTRA5") (pin "4") (pinfunction "4_4") (pintype "passive"))
      (node (ref "ULTRA6") (pin "4") (pinfunction "4_4") (pintype "passive"))
    )
    (net (code "99") (name "Net-(JTAG-Pad1)") (class "Default")
      (node (ref "JTAG") (pin "1") (pinfunction "1_1") (pintype "passive"))
      (node (ref "R8") (pin "2") (pinfunction "2_2") (pintype "passive"))
    )
    (net (code "100") (name "Net-(LED2-PadA)") (class "Default")
      (node (ref "LED2") (pin "A") (pinfunction "A_A") (pintype "passive"))
      (node (ref "R10") (pin "1") (pinfunction "1_1") (pintype "passive"))
    )
    (net (code "101") (name "Net-(MSP432P401R-AVCC1)") (class "Default")
      (node (ref "C3") (pin "1") (pinfunction "1_1") (pintype "passive"))
      (node (ref "C4") (pin "1") (pinfunction "1_1") (pintype "passive"))
      (node (ref "MSP432P401R") (pin "45") (pinfunction "AVCC1_45") (pintype "power_in"))
      (node (ref "MSP432P401R") (pin "87") (pinfunction "AVCC2_87") (pintype "power_in"))
      (node (ref "R3") (pin "2") (pinfunction "2_2") (pintype "passive"))
    )
    (net (code "102") (name "Net-(POWER_LED-PadA)") (class "Default")
      (node (ref "POWER_LED") (pin "A") (pinfunction "A_A") (pintype "passive"))
      (node (ref "R9") (pin "1") (pinfunction "1_1") (pintype "passive"))
    )
    (net (code "103") (name "P2.2_RX") (class "Default")
      (node (ref "MSP432P401R") (pin "18") (pinfunction "P2.2/PM_UCA1RXD/PM_UCA1SOMI_18") (pintype "power_in"))
      (node (ref "TP3") (pin "TP") (pinfunction "TP_TP") (pintype "input"))
      (node (ref "U$3") (pin "4") (pinfunction "P$4_4") (pintype "bidirectional"))
    )
    (net (code "104") (name "P2.7_PWM_J4.40") (class "Default")
      (node (ref "MSP432P401R") (pin "23") (pinfunction "P2.7/PM_TA0.4_23") (pintype "power_in"))
      (node (ref "NAZE32_PINHEAD") (pin "7") (pinfunction "7_7") (pintype "passive"))
    )
    (net (code "105") (name "P3.6_SDA") (class "Default")
      (node (ref "MSP432P401R") (pin "38") (pinfunction "P3.6/PM_UCB2SIMO/PM_UCB2SDA_38") (pintype "power_in"))
    )
    (net (code "106") (name "P3.7_SCL") (class "Default")
      (node (ref "MSP432P401R") (pin "39") (pinfunction "P3.7/PM_UCB2SOMI/PM_UCB2SCL_39") (pintype "power_in"))
    )
    (net (code "107") (name "P4.0_GPIO") (class "Default")
      (node (ref "GPIO_EXTRA") (pin "1") (pinfunction "1_1") (pintype "passive"))
      (node (ref "MSP432P401R") (pin "56") (pinfunction "P4.0/A13_56") (pintype "power_in"))
    )
    (net (code "108") (name "P4.1_GPIO") (class "Default")
      (node (ref "GPIO_EXTRA") (pin "2") (pinfunction "2_2") (pintype "passive"))
      (node (ref "MSP432P401R") (pin "57") (pinfunction "P4.1/A12_57") (pintype "power_in"))
    )
    (net (code "109") (name "P4.5_GPIO") (class "Default")
      (node (ref "GPIO_EXTRA") (pin "3") (pinfunction "3_3") (pintype "passive"))
      (node (ref "MSP432P401R") (pin "61") (pinfunction "P4.5/A8_61") (pintype "power_in"))
    )
    (net (code "110") (name "P4.6_GPIO") (class "Default")
      (node (ref "GPIO_EXTRA") (pin "4") (pinfunction "4_4") (pintype "passive"))
      (node (ref "MSP432P401R") (pin "62") (pinfunction "P4.6/A7_62") (pintype "power_in"))
    )
    (net (code "111") (name "P4.7_GPIO") (class "Default")
      (node (ref "GPIO_EXTRA") (pin "5") (pinfunction "5_5") (pintype "passive"))
      (node (ref "MSP432P401R") (pin "63") (pinfunction "P4.7/A6_63") (pintype "power_in"))
    )
    (net (code "112") (name "VBAT_TX") (class "Default")
      (node (ref "BATTERY_FC_PINS") (pin "1") (pinfunction "1_1") (pintype "passive"))
      (node (ref "U$3") (pin "5") (pinfunction "P$5_5") (pintype "bidirectional"))
    )
    (net (code "113") (name "unconnected-(MSP432P401R-P7.3{slash}PM_TA0.0-Pad91)") (class "Default")
      (node (ref "MSP432P401R") (pin "91") (pinfunction "P7.3/PM_TA0.0_91") (pintype "power_in"))
    )
    (net (code "114") (name "unconnected-(U$2-NC_4-Pad4)") (class "Default")
      (node (ref "U$2") (pin "4") (pinfunction "NC_4_4") (pintype "bidirectional"))
    )
    (net (code "115") (name "unconnected-(U$3-P$1-Pad1)") (class "Default")
      (node (ref "U$3") (pin "1") (pinfunction "P$1_1") (pintype "bidirectional"))
    )
    (net (code "116") (name "unconnected-(U$3-P$8-Pad8)") (class "Default")
      (node (ref "U$3") (pin "8") (pinfunction "P$8_8") (pintype "bidirectional"))
    )
  )
)
